# Messchieber.net
KiCad netlist of a schematic drawn in EAGLE
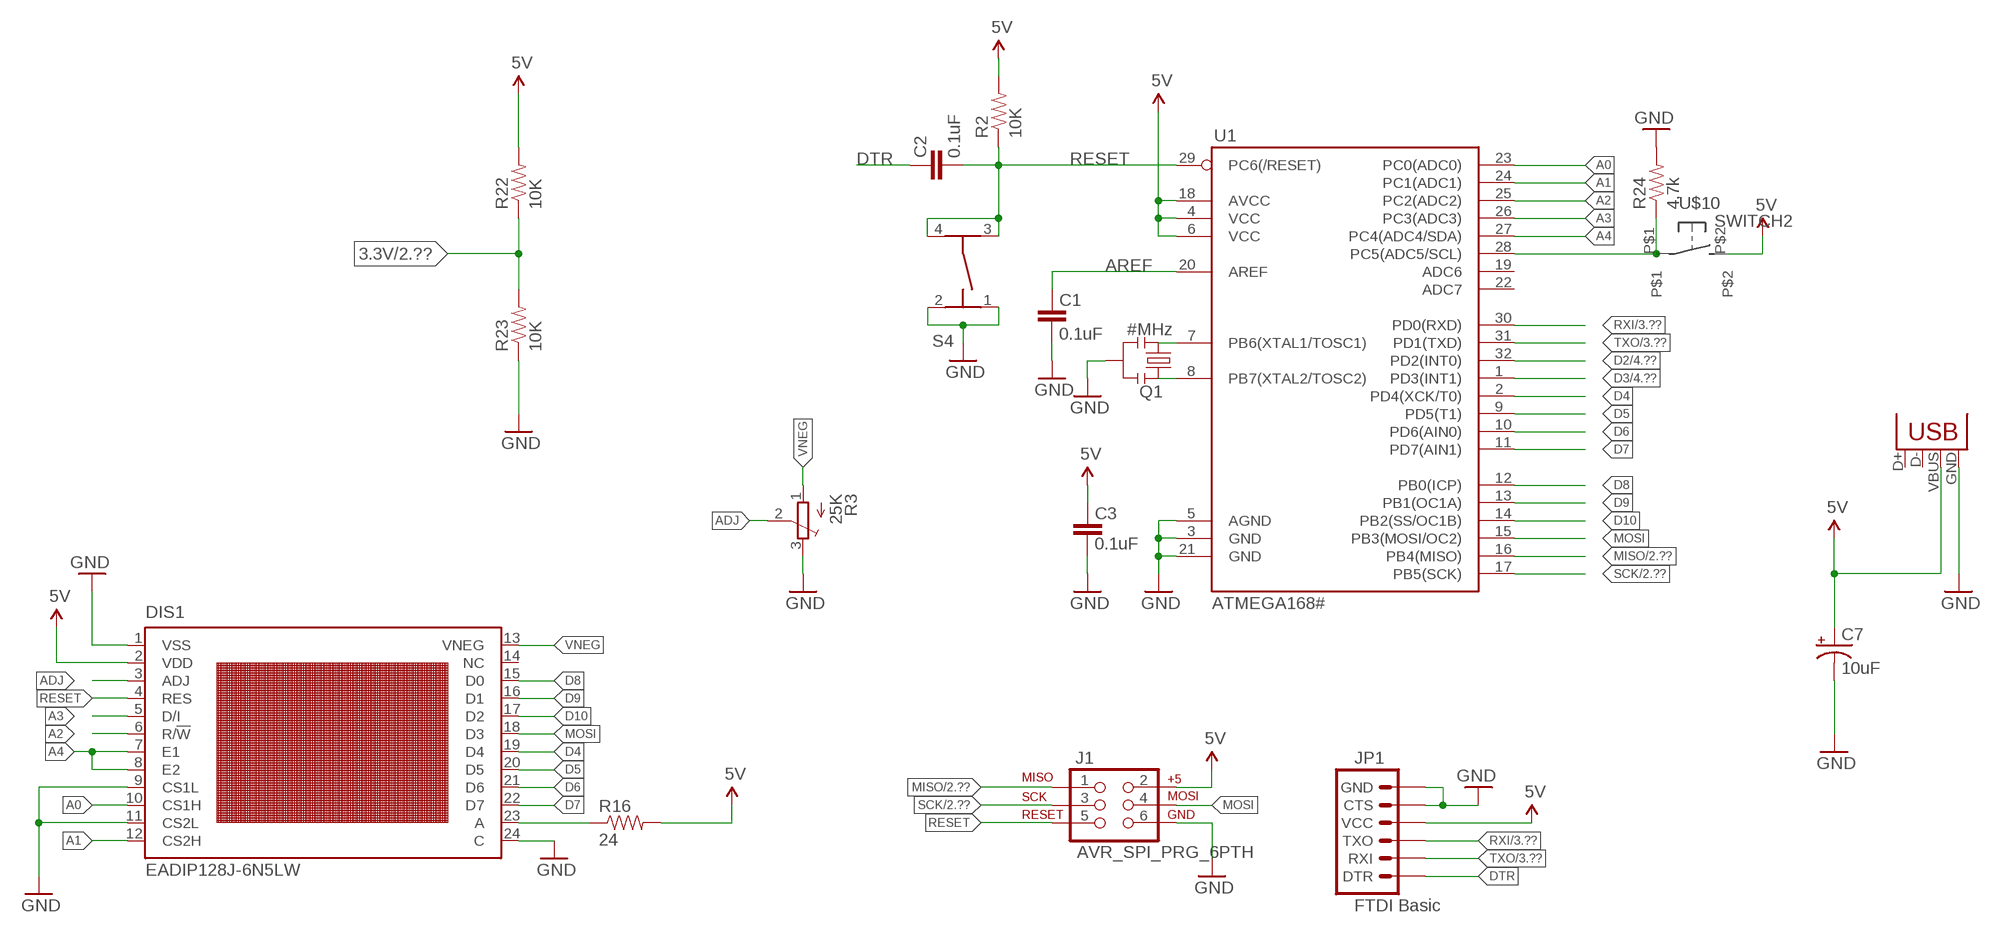
[diagram p0: schematic, sheet 1]
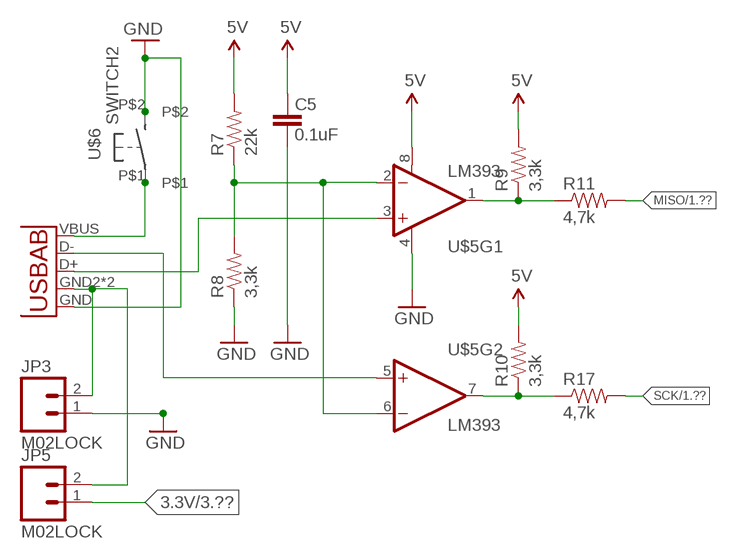
[diagram p1: schematic, sheet 2]
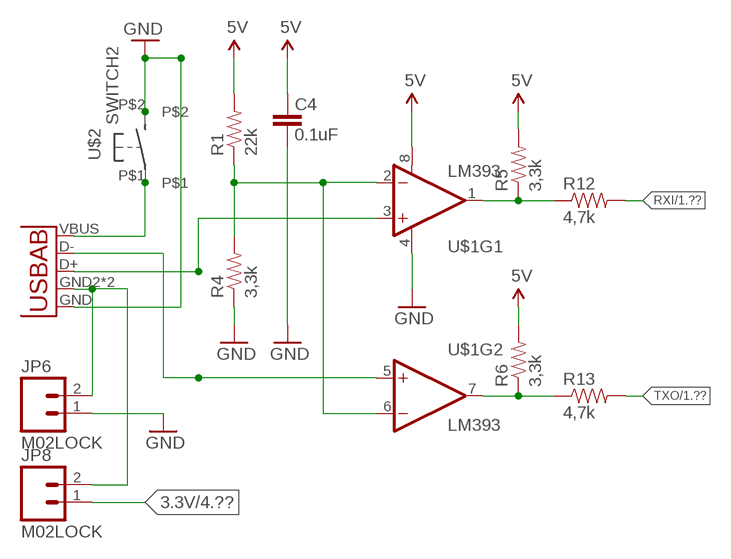
[diagram p2: schematic, sheet 3]
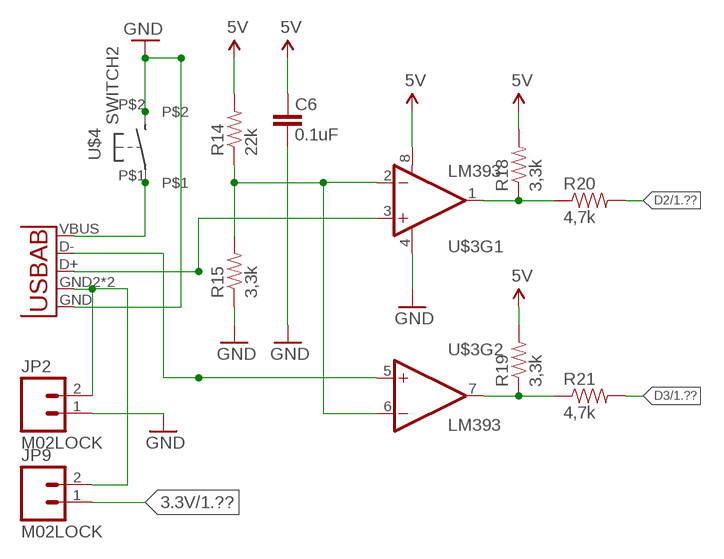
[diagram p3: schematic, sheet 4]

(export (version "E")
  (design (tool "Eeschema 10.0.6"))
  (components
    (comp (ref "C5")
      (value "0.1uF")
      (footprint "eagle-import:0805")
      (libsource (lib "eagle-import") (part "CAP0805"))
    )
    (comp (ref "JP3")
      (value "M02LOCK")
      (footprint "eagle-import:1X02_LOCK")
      (libsource (lib "eagle-import") (part "M02LOCK"))
    )
    (comp (ref "JP5")
      (value "M02LOCK")
      (footprint "eagle-import:1X02_LOCK")
      (libsource (lib "eagle-import") (part "M02LOCK"))
    )
    (comp (ref "R7")
      (value "22k")
      (footprint "eagle-import:0805")
      (libsource (lib "eagle-import") (part "RESISTOR"))
    )
    (comp (ref "R8")
      (value "3,3k")
      (footprint "eagle-import:0805")
      (libsource (lib "eagle-import") (part "RESISTOR"))
    )
    (comp (ref "R9")
      (value "3,3k")
      (footprint "eagle-import:0805")
      (libsource (lib "eagle-import") (part "RESISTOR"))
    )
    (comp (ref "R10")
      (value "3,3k")
      (footprint "eagle-import:0805")
      (libsource (lib "eagle-import") (part "RESISTOR"))
    )
    (comp (ref "R11")
      (value "4,7k")
      (footprint "eagle-import:0805")
      (libsource (lib "eagle-import") (part "RESISTOR"))
    )
    (comp (ref "R17")
      (value "4,7k")
      (footprint "eagle-import:0805")
      (libsource (lib "eagle-import") (part "RESISTOR"))
    )
    (comp (ref "U$5")
      (value "LM393")
      (footprint "eagle-import:SO08")
      (libsource (lib "eagle-import") (part "LM393"))
    )
    (comp (ref "U$6")
      (value "SWITCH2")
      (footprint "eagle-import:SWITCH2")
      (libsource (lib "eagle-import") (part "SWITCH2"))
    )
    (comp (ref "U$7")
      (value "USB-A")
      (footprint "eagle-import:USB-A")
      (libsource (lib "eagle-import") (part "USB-A"))
    )
    (comp (ref "C4")
      (value "0.1uF")
      (footprint "eagle-import:0805")
      (libsource (lib "eagle-import") (part "CAP0805"))
    )
    (comp (ref "JP6")
      (value "M02LOCK")
      (footprint "eagle-import:1X02_LOCK")
      (libsource (lib "eagle-import") (part "M02LOCK"))
    )
    (comp (ref "JP8")
      (value "M02LOCK")
      (footprint "eagle-import:1X02_LOCK")
      (libsource (lib "eagle-import") (part "M02LOCK"))
    )
    (comp (ref "R1")
      (value "22k")
      (footprint "eagle-import:0805")
      (libsource (lib "eagle-import") (part "RESISTOR"))
    )
    (comp (ref "R4")
      (value "3,3k")
      (footprint "eagle-import:0805")
      (libsource (lib "eagle-import") (part "RESISTOR"))
    )
    (comp (ref "R5")
      (value "3,3k")
      (footprint "eagle-import:0805")
      (libsource (lib "eagle-import") (part "RESISTOR"))
    )
    (comp (ref "R6")
      (value "3,3k")
      (footprint "eagle-import:0805")
      (libsource (lib "eagle-import") (part "RESISTOR"))
    )
    (comp (ref "R12")
      (value "4,7k")
      (footprint "eagle-import:0805")
      (libsource (lib "eagle-import") (part "RESISTOR"))
    )
    (comp (ref "R13")
      (value "4,7k")
      (footprint "eagle-import:0805")
      (libsource (lib "eagle-import") (part "RESISTOR"))
    )
    (comp (ref "U$1")
      (value "LM393")
      (footprint "eagle-import:SO08")
      (libsource (lib "eagle-import") (part "LM393"))
    )
    (comp (ref "U$2")
      (value "SWITCH2")
      (footprint "eagle-import:SWITCH2")
      (libsource (lib "eagle-import") (part "SWITCH2"))
    )
    (comp (ref "U$8")
      (value "USB-A")
      (footprint "eagle-import:USB-A")
      (libsource (lib "eagle-import") (part "USB-A"))
    )
    (comp (ref "C6")
      (value "0.1uF")
      (footprint "eagle-import:0805")
      (libsource (lib "eagle-import") (part "CAP0805"))
    )
    (comp (ref "JP2")
      (value "M02LOCK")
      (footprint "eagle-import:1X02_LOCK")
      (libsource (lib "eagle-import") (part "M02LOCK"))
    )
    (comp (ref "JP9")
      (value "M02LOCK")
      (footprint "eagle-import:1X02_LOCK")
      (libsource (lib "eagle-import") (part "M02LOCK"))
    )
    (comp (ref "R14")
      (value "22k")
      (footprint "eagle-import:0805")
      (libsource (lib "eagle-import") (part "RESISTOR"))
    )
    (comp (ref "R15")
      (value "3,3k")
      (footprint "eagle-import:0805")
      (libsource (lib "eagle-import") (part "RESISTOR"))
    )
    (comp (ref "R18")
      (value "3,3k")
      (footprint "eagle-import:0805")
      (libsource (lib "eagle-import") (part "RESISTOR"))
    )
    (comp (ref "R19")
      (value "3,3k")
      (footprint "eagle-import:0805")
      (libsource (lib "eagle-import") (part "RESISTOR"))
    )
    (comp (ref "R20")
      (value "4,7k")
      (footprint "eagle-import:0805")
      (libsource (lib "eagle-import") (part "RESISTOR"))
    )
    (comp (ref "R21")
      (value "4,7k")
      (footprint "eagle-import:0805")
      (libsource (lib "eagle-import") (part "RESISTOR"))
    )
    (comp (ref "U$3")
      (value "LM393")
      (footprint "eagle-import:SO08")
      (libsource (lib "eagle-import") (part "LM393"))
    )
    (comp (ref "U$4")
      (value "SWITCH2")
      (footprint "eagle-import:SWITCH2")
      (libsource (lib "eagle-import") (part "SWITCH2"))
    )
    (comp (ref "U$9")
      (value "USB-A")
      (footprint "eagle-import:USB-A")
      (libsource (lib "eagle-import") (part "USB-A"))
    )
    (comp (ref "C1")
      (value "0.1uF")
      (footprint "eagle-import:0805")
      (libsource (lib "eagle-import") (part "CAP0805"))
    )
    (comp (ref "C2")
      (value "0.1uF")
      (footprint "eagle-import:0805")
      (libsource (lib "eagle-import") (part "CAP0805"))
    )
    (comp (ref "C3")
      (value "0.1uF")
      (footprint "eagle-import:0805")
      (libsource (lib "eagle-import") (part "CAP0805"))
    )
    (comp (ref "C7")
      (value "10uF")
      (footprint "eagle-import:EIA3216")
      (libsource (lib "eagle-import") (part "10UF-16V-10%(TANT)"))
    )
    (comp (ref "DIS1")
      (value "EADIP128J-6N5LW")
      (footprint "eagle-import:LCD-DIP128-64")
      (libsource (lib "eagle-import") (part "EADIP128-6N5LWJ"))
    )
    (comp (ref "J1")
      (value "AVR_SPI_PRG_6PTH")
      (footprint "eagle-import:2X3")
      (libsource (lib "eagle-import") (part "AVR_SPI_PRG_6PTH"))
    )
    (comp (ref "JP1")
      (value "FTDI Basic")
      (footprint "eagle-import:1X06")
      (libsource (lib "eagle-import") (part "ARDUINO_SERIAL_PROGRAMPTH"))
    )
    (comp (ref "JP7")
      (value "USB-SMD-NS")
      (footprint "eagle-import:USB-MINIB-NOSTOP")
      (libsource (lib "eagle-import") (part "USB-SMD-NS"))
    )
    (comp (ref "Q1")
      (value "#MHz")
      (footprint "eagle-import:RESONATOR-SMD")
      (libsource (lib "eagle-import") (part "RESONATORSMD"))
    )
    (comp (ref "R2")
      (value "10K")
      (footprint "eagle-import:0805")
      (libsource (lib "eagle-import") (part "RESISTOR"))
    )
    (comp (ref "R3")
      (value "25K")
      (footprint "eagle-import:SM-42_43A")
      (libsource (lib "eagle-import") (part "TRIM_EU-SM-42/43A"))
    )
    (comp (ref "R16")
      (value "24")
      (footprint "eagle-import:0805")
      (libsource (lib "eagle-import") (part "RESISTOR"))
    )
    (comp (ref "R22")
      (value "10K")
      (footprint "eagle-import:0805")
      (libsource (lib "eagle-import") (part "RESISTOR"))
    )
    (comp (ref "R23")
      (value "10K")
      (footprint "eagle-import:0805")
      (libsource (lib "eagle-import") (part "RESISTOR"))
    )
    (comp (ref "R24")
      (value "4,7k")
      (footprint "eagle-import:0805")
      (libsource (lib "eagle-import") (part "RESISTOR"))
    )
    (comp (ref "S4")
      (value "TASTER-9314_SMD")
      (footprint "eagle-import:TASTER-9314_SMD")
      (libsource (lib "eagle-import") (part "TASTER-9314_SMD"))
    )
    (comp (ref "U$10")
      (value "SWITCH2")
      (footprint "eagle-import:SWITCH2")
      (libsource (lib "eagle-import") (part "SWITCH2"))
    )
    (comp (ref "U1")
      (value "ATMEGA168#")
      (footprint "eagle-import:TQFP32-08")
      (libsource (lib "eagle-import") (part "ATMEGA168"))
    )
  )
  (nets
    (net (code "1") (name "3.3V") (class "Default")
      (node (ref "JP5") (pin "1") (pinfunction "1_1") (pintype "passive"))
      (node (ref "JP8") (pin "1") (pinfunction "1_1") (pintype "passive"))
      (node (ref "JP9") (pin "1") (pinfunction "1_1") (pintype "passive"))
      (node (ref "R22") (pin "1") (pinfunction "1_1") (pintype "passive"))
      (node (ref "R23") (pin "2") (pinfunction "2_2") (pintype "passive"))
    )
    (net (code "2") (name "5V") (class "Default")
      (node (ref "C3") (pin "2") (pinfunction "2_2") (pintype "passive"))
      (node (ref "C4") (pin "2") (pinfunction "2_2") (pintype "passive"))
      (node (ref "C5") (pin "2") (pinfunction "2_2") (pintype "passive"))
      (node (ref "C6") (pin "2") (pinfunction "2_2") (pintype "passive"))
      (node (ref "C7") (pin "A") (pinfunction "+_A") (pintype "passive"))
      (node (ref "DIS1") (pin "2") (pinfunction "VDD_2") (pintype "power_in"))
      (node (ref "J1") (pin "2") (pinfunction "2_2") (pintype "passive"))
      (node (ref "JP1") (pin "4") (pinfunction "VCC_4") (pintype "passive"))
      (node (ref "JP7") (pin "VBUS") (pinfunction "VBUS_VBUS") (pintype "bidirectional"))
      (node (ref "R1") (pin "2") (pinfunction "2_2") (pintype "passive"))
      (node (ref "R10") (pin "2") (pinfunction "2_2") (pintype "passive"))
      (node (ref "R14") (pin "2") (pinfunction "2_2") (pintype "passive"))
      (node (ref "R16") (pin "2") (pinfunction "2_2") (pintype "passive"))
      (node (ref "R18") (pin "2") (pinfunction "2_2") (pintype "passive"))
      (node (ref "R19") (pin "2") (pinfunction "2_2") (pintype "passive"))
      (node (ref "R2") (pin "2") (pinfunction "2_2") (pintype "passive"))
      (node (ref "R22") (pin "2") (pinfunction "2_2") (pintype "passive"))
      (node (ref "R5") (pin "2") (pinfunction "2_2") (pintype "passive"))
      (node (ref "R6") (pin "2") (pinfunction "2_2") (pintype "passive"))
      (node (ref "R7") (pin "2") (pinfunction "2_2") (pintype "passive"))
      (node (ref "R9") (pin "2") (pinfunction "2_2") (pintype "passive"))
      (node (ref "U$1") (pin "8") (pinfunction "V+_8") (pintype "power_in"))
      (node (ref "U$10") (pin "P$2") (pinfunction "P$2_P$2") (pintype "bidirectional"))
      (node (ref "U$3") (pin "8") (pinfunction "V+_8") (pintype "power_in"))
      (node (ref "U$5") (pin "8") (pinfunction "V+_8") (pintype "power_in"))
      (node (ref "U1") (pin "18") (pinfunction "AVCC_18") (pintype "bidirectional"))
      (node (ref "U1") (pin "4") (pinfunction "VCC_4") (pintype "bidirectional"))
      (node (ref "U1") (pin "6") (pinfunction "VCC_6") (pintype "bidirectional"))
    )
    (net (code "3") (name "A0") (class "Default")
      (node (ref "DIS1") (pin "10") (pinfunction "CS1H_10") (pintype "input"))
      (node (ref "U1") (pin "23") (pinfunction "PC0(ADC0)_23") (pintype "bidirectional"))
    )
    (net (code "4") (name "A1") (class "Default")
      (node (ref "DIS1") (pin "12") (pinfunction "CS2H_12") (pintype "input"))
      (node (ref "U1") (pin "24") (pinfunction "PC1(ADC1)_24") (pintype "bidirectional"))
    )
    (net (code "5") (name "A2") (class "Default")
      (node (ref "DIS1") (pin "6") (pinfunction "R/~{W}_6") (pintype "input"))
      (node (ref "U1") (pin "25") (pinfunction "PC2(ADC2)_25") (pintype "bidirectional"))
    )
    (net (code "6") (name "A3") (class "Default")
      (node (ref "DIS1") (pin "5") (pinfunction "D/I_5") (pintype "input"))
      (node (ref "U1") (pin "26") (pinfunction "PC3(ADC3)_26") (pintype "bidirectional"))
    )
    (net (code "7") (name "A4") (class "Default")
      (node (ref "DIS1") (pin "7") (pinfunction "E1_7") (pintype "input"))
      (node (ref "DIS1") (pin "8") (pinfunction "E2_8") (pintype "input"))
      (node (ref "U1") (pin "27") (pinfunction "PC4(ADC4/SDA)_27") (pintype "bidirectional"))
    )
    (net (code "8") (name "ADJ") (class "Default")
      (node (ref "DIS1") (pin "3") (pinfunction "ADJ_3") (pintype "input"))
      (node (ref "R3") (pin "2") (pinfunction "S_2") (pintype "passive"))
    )
    (net (code "9") (name "AREF") (class "Default")
      (node (ref "C1") (pin "2") (pinfunction "2_2") (pintype "passive"))
      (node (ref "U1") (pin "20") (pinfunction "AREF_20") (pintype "bidirectional"))
    )
    (net (code "10") (name "D2") (class "Default")
      (node (ref "R20") (pin "2") (pinfunction "2_2") (pintype "passive"))
      (node (ref "U1") (pin "32") (pinfunction "PD2(INT0)_32") (pintype "bidirectional"))
    )
    (net (code "11") (name "D3") (class "Default")
      (node (ref "R21") (pin "2") (pinfunction "2_2") (pintype "passive"))
      (node (ref "U1") (pin "1") (pinfunction "PD3(INT1)_1") (pintype "bidirectional"))
    )
    (net (code "12") (name "D4") (class "Default")
      (node (ref "DIS1") (pin "19") (pinfunction "D4_19") (pintype "bidirectional"))
      (node (ref "U1") (pin "2") (pinfunction "PD4(XCK/T0)_2") (pintype "bidirectional"))
    )
    (net (code "13") (name "D5") (class "Default")
      (node (ref "DIS1") (pin "20") (pinfunction "D5_20") (pintype "bidirectional"))
      (node (ref "U1") (pin "9") (pinfunction "PD5(T1)_9") (pintype "bidirectional"))
    )
    (net (code "14") (name "D6") (class "Default")
      (node (ref "DIS1") (pin "21") (pinfunction "D6_21") (pintype "bidirectional"))
      (node (ref "U1") (pin "10") (pinfunction "PD6(AIN0)_10") (pintype "bidirectional"))
    )
    (net (code "15") (name "D7") (class "Default")
      (node (ref "DIS1") (pin "22") (pinfunction "D7_22") (pintype "bidirectional"))
      (node (ref "U1") (pin "11") (pinfunction "PD7(AIN1)_11") (pintype "bidirectional"))
    )
    (net (code "16") (name "D8") (class "Default")
      (node (ref "DIS1") (pin "15") (pinfunction "D0_15") (pintype "bidirectional"))
      (node (ref "U1") (pin "12") (pinfunction "PB0(ICP)_12") (pintype "bidirectional"))
    )
    (net (code "17") (name "D9") (class "Default")
      (node (ref "DIS1") (pin "16") (pinfunction "D1_16") (pintype "bidirectional"))
      (node (ref "U1") (pin "13") (pinfunction "PB1(OC1A)_13") (pintype "bidirectional"))
    )
    (net (code "18") (name "D10") (class "Default")
      (node (ref "DIS1") (pin "17") (pinfunction "D2_17") (pintype "bidirectional"))
      (node (ref "U1") (pin "14") (pinfunction "PB2(SS/OC1B)_14") (pintype "bidirectional"))
    )
    (net (code "19") (name "DTR") (class "Default")
      (node (ref "C2") (pin "2") (pinfunction "2_2") (pintype "passive"))
      (node (ref "JP1") (pin "1") (pinfunction "DTR_1") (pintype "passive"))
    )
    (net (code "20") (name "GND") (class "Default")
      (node (ref "C1") (pin "1") (pinfunction "1_1") (pintype "passive"))
      (node (ref "C3") (pin "1") (pinfunction "1_1") (pintype "passive"))
      (node (ref "C4") (pin "1") (pinfunction "1_1") (pintype "passive"))
      (node (ref "C5") (pin "1") (pinfunction "1_1") (pintype "passive"))
      (node (ref "C6") (pin "1") (pinfunction "1_1") (pintype "passive"))
      (node (ref "C7") (pin "C") (pinfunction "-_C") (pintype "passive"))
      (node (ref "DIS1") (pin "1") (pinfunction "VSS_1") (pintype "power_in"))
      (node (ref "DIS1") (pin "11") (pinfunction "CS2L_11") (pintype "input"))
      (node (ref "DIS1") (pin "24") (pinfunction "C_24") (pintype "passive"))
      (node (ref "DIS1") (pin "9") (pinfunction "CS1L_9") (pintype "input"))
      (node (ref "J1") (pin "6") (pinfunction "6_6") (pintype "passive"))
      (node (ref "JP1") (pin "5") (pinfunction "CTS_5") (pintype "passive"))
      (node (ref "JP1") (pin "6") (pinfunction "GND_6") (pintype "passive"))
      (node (ref "JP2") (pin "1") (pinfunction "1_1") (pintype "passive"))
      (node (ref "JP3") (pin "1") (pinfunction "1_1") (pintype "passive"))
      (node (ref "JP6") (pin "1") (pinfunction "1_1") (pintype "passive"))
      (node (ref "JP7") (pin "GND") (pinfunction "GND_GND") (pintype "bidirectional"))
      (node (ref "Q1") (pin "2") (pinfunction "2_2") (pintype "passive"))
      (node (ref "R15") (pin "1") (pinfunction "1_1") (pintype "passive"))
      (node (ref "R23") (pin "1") (pinfunction "1_1") (pintype "passive"))
      (node (ref "R24") (pin "2") (pinfunction "2_2") (pintype "passive"))
      (node (ref "R3") (pin "3") (pinfunction "E_3") (pintype "passive"))
      (node (ref "R4") (pin "1") (pinfunction "1_1") (pintype "passive"))
      (node (ref "R8") (pin "1") (pinfunction "1_1") (pintype "passive"))
      (node (ref "S4") (pin "1") (pinfunction "1_1") (pintype "passive"))
      (node (ref "S4") (pin "2") (pinfunction "2_2") (pintype "passive"))
      (node (ref "U$1") (pin "4") (pinfunction "V-_4") (pintype "power_in"))
      (node (ref "U$2") (pin "P$2") (pinfunction "P$2_P$2") (pintype "bidirectional"))
      (node (ref "U$3") (pin "4") (pinfunction "V-_4") (pintype "power_in"))
      (node (ref "U$4") (pin "P$2") (pinfunction "P$2_P$2") (pintype "bidirectional"))
      (node (ref "U$5") (pin "4") (pinfunction "V-_4") (pintype "power_in"))
      (node (ref "U$6") (pin "P$2") (pinfunction "P$2_P$2") (pintype "bidirectional"))
      (node (ref "U$7") (pin "GND") (pinfunction "GND_GND") (pintype "bidirectional"))
      (node (ref "U$8") (pin "GND") (pinfunction "GND_GND") (pintype "bidirectional"))
      (node (ref "U$9") (pin "GND") (pinfunction "GND_GND") (pintype "bidirectional"))
      (node (ref "U1") (pin "21") (pinfunction "GND_21") (pintype "bidirectional"))
      (node (ref "U1") (pin "3") (pinfunction "GND_3") (pintype "bidirectional"))
      (node (ref "U1") (pin "5") (pinfunction "AGND_5") (pintype "bidirectional"))
    )
    (net (code "21") (name "MISO") (class "Default")
      (node (ref "J1") (pin "1") (pinfunction "1_1") (pintype "passive"))
      (node (ref "R11") (pin "2") (pinfunction "2_2") (pintype "passive"))
      (node (ref "U1") (pin "16") (pinfunction "PB4(MISO)_16") (pintype "bidirectional"))
    )
    (net (code "22") (name "MOSI") (class "Default")
      (node (ref "DIS1") (pin "18") (pinfunction "D3_18") (pintype "bidirectional"))
      (node (ref "J1") (pin "4") (pinfunction "4_4") (pintype "passive"))
      (node (ref "U1") (pin "15") (pinfunction "PB3(MOSI/OC2)_15") (pintype "bidirectional"))
    )
    (net (code "23") (name "Net-(DIS1-A)") (class "Default")
      (node (ref "DIS1") (pin "23") (pinfunction "A_23") (pintype "passive"))
      (node (ref "R16") (pin "1") (pinfunction "1_1") (pintype "passive"))
    )
    (net (code "24") (name "Net-(JP2-Pad2)") (class "Default")
      (node (ref "JP2") (pin "2") (pinfunction "2_2") (pintype "passive"))
      (node (ref "JP9") (pin "2") (pinfunction "2_2") (pintype "passive"))
      (node (ref "U$9") (pin "GND2") (pinfunction "USBID_GND2") (pintype "bidirectional"))
      (node (ref "U$9") (pin "GND3") (pinfunction "USBID_GND3") (pintype "bidirectional"))
    )
    (net (code "25") (name "Net-(JP3-Pad2)") (class "Default")
      (node (ref "JP3") (pin "2") (pinfunction "2_2") (pintype "passive"))
      (node (ref "JP5") (pin "2") (pinfunction "2_2") (pintype "passive"))
      (node (ref "U$7") (pin "GND2") (pinfunction "USBID_GND2") (pintype "bidirectional"))
      (node (ref "U$7") (pin "GND3") (pinfunction "USBID_GND3") (pintype "bidirectional"))
    )
    (net (code "26") (name "Net-(JP6-Pad2)") (class "Default")
      (node (ref "JP6") (pin "2") (pinfunction "2_2") (pintype "passive"))
      (node (ref "JP8") (pin "2") (pinfunction "2_2") (pintype "passive"))
      (node (ref "U$8") (pin "GND2") (pinfunction "USBID_GND2") (pintype "bidirectional"))
      (node (ref "U$8") (pin "GND3") (pinfunction "USBID_GND3") (pintype "bidirectional"))
    )
    (net (code "27") (name "Net-(U$1A-+IN)") (class "Default")
      (node (ref "U$1") (pin "3") (pinfunction "+IN_3") (pintype "input"))
      (node (ref "U$8") (pin "D+") (pinfunction "D+_D+") (pintype "bidirectional"))
    )
    (net (code "28") (name "Net-(U$1A--IN)") (class "Default")
      (node (ref "R1") (pin "1") (pinfunction "1_1") (pintype "passive"))
      (node (ref "R4") (pin "2") (pinfunction "2_2") (pintype "passive"))
      (node (ref "U$1") (pin "2") (pinfunction "-IN_2") (pintype "input"))
      (node (ref "U$1") (pin "6") (pinfunction "-IN_6") (pintype "input"))
    )
    (net (code "29") (name "Net-(U$1A-OUT)") (class "Default")
      (node (ref "R12") (pin "1") (pinfunction "1_1") (pintype "passive"))
      (node (ref "R5") (pin "1") (pinfunction "1_1") (pintype "passive"))
      (node (ref "U$1") (pin "1") (pinfunction "OUT_1") (pintype "output"))
    )
    (net (code "30") (name "Net-(U$1B-+IN)") (class "Default")
      (node (ref "U$1") (pin "5") (pinfunction "+IN_5") (pintype "input"))
      (node (ref "U$8") (pin "D-") (pinfunction "D-_D-") (pintype "bidirectional"))
    )
    (net (code "31") (name "Net-(U$1B-OUT)") (class "Default")
      (node (ref "R13") (pin "1") (pinfunction "1_1") (pintype "passive"))
      (node (ref "R6") (pin "1") (pinfunction "1_1") (pintype "passive"))
      (node (ref "U$1") (pin "7") (pinfunction "OUT_7") (pintype "output"))
    )
    (net (code "32") (name "Net-(U$2-PadP$1)") (class "Default")
      (node (ref "U$2") (pin "P$1") (pinfunction "P$1_P$1") (pintype "bidirectional"))
      (node (ref "U$8") (pin "VBUS") (pinfunction "VBUS_VBUS") (pintype "bidirectional"))
    )
    (net (code "33") (name "Net-(U$3A-+IN)") (class "Default")
      (node (ref "U$3") (pin "3") (pinfunction "+IN_3") (pintype "input"))
      (node (ref "U$9") (pin "D+") (pinfunction "D+_D+") (pintype "bidirectional"))
    )
    (net (code "34") (name "Net-(U$3A--IN)") (class "Default")
      (node (ref "R14") (pin "1") (pinfunction "1_1") (pintype "passive"))
      (node (ref "R15") (pin "2") (pinfunction "2_2") (pintype "passive"))
      (node (ref "U$3") (pin "2") (pinfunction "-IN_2") (pintype "input"))
      (node (ref "U$3") (pin "6") (pinfunction "-IN_6") (pintype "input"))
    )
    (net (code "35") (name "Net-(U$3A-OUT)") (class "Default")
      (node (ref "R18") (pin "1") (pinfunction "1_1") (pintype "passive"))
      (node (ref "R20") (pin "1") (pinfunction "1_1") (pintype "passive"))
      (node (ref "U$3") (pin "1") (pinfunction "OUT_1") (pintype "output"))
    )
    (net (code "36") (name "Net-(U$3B-+IN)") (class "Default")
      (node (ref "U$3") (pin "5") (pinfunction "+IN_5") (pintype "input"))
      (node (ref "U$9") (pin "D-") (pinfunction "D-_D-") (pintype "bidirectional"))
    )
    (net (code "37") (name "Net-(U$3B-OUT)") (class "Default")
      (node (ref "R19") (pin "1") (pinfunction "1_1") (pintype "passive"))
      (node (ref "R21") (pin "1") (pinfunction "1_1") (pintype "passive"))
      (node (ref "U$3") (pin "7") (pinfunction "OUT_7") (pintype "output"))
    )
    (net (code "38") (name "Net-(U$4-PadP$1)") (class "Default")
      (node (ref "U$4") (pin "P$1") (pinfunction "P$1_P$1") (pintype "bidirectional"))
      (node (ref "U$9") (pin "VBUS") (pinfunction "VBUS_VBUS") (pintype "bidirectional"))
    )
    (net (code "39") (name "Net-(U$5A-+IN)") (class "Default")
      (node (ref "U$5") (pin "3") (pinfunction "+IN_3") (pintype "input"))
      (node (ref "U$7") (pin "D+") (pinfunction "D+_D+") (pintype "bidirectional"))
    )
    (net (code "40") (name "Net-(U$5A--IN)") (class "Default")
      (node (ref "R7") (pin "1") (pinfunction "1_1") (pintype "passive"))
      (node (ref "R8") (pin "2") (pinfunction "2_2") (pintype "passive"))
      (node (ref "U$5") (pin "2") (pinfunction "-IN_2") (pintype "input"))
      (node (ref "U$5") (pin "6") (pinfunction "-IN_6") (pintype "input"))
    )
    (net (code "41") (name "Net-(U$5A-OUT)") (class "Default")
      (node (ref "R11") (pin "1") (pinfunction "1_1") (pintype "passive"))
      (node (ref "R9") (pin "1") (pinfunction "1_1") (pintype "passive"))
      (node (ref "U$5") (pin "1") (pinfunction "OUT_1") (pintype "output"))
    )
    (net (code "42") (name "Net-(U$5B-+IN)") (class "Default")
      (node (ref "U$5") (pin "5") (pinfunction "+IN_5") (pintype "input"))
      (node (ref "U$7") (pin "D-") (pinfunction "D-_D-") (pintype "bidirectional"))
    )
    (net (code "43") (name "Net-(U$5B-OUT)") (class "Default")
      (node (ref "R10") (pin "1") (pinfunction "1_1") (pintype "passive"))
      (node (ref "R17") (pin "1") (pinfunction "1_1") (pintype "passive"))
      (node (ref "U$5") (pin "7") (pinfunction "OUT_7") (pintype "output"))
    )
    (net (code "44") (name "Net-(U$6-PadP$1)") (class "Default")
      (node (ref "U$6") (pin "P$1") (pinfunction "P$1_P$1") (pintype "bidirectional"))
      (node (ref "U$7") (pin "VBUS") (pinfunction "VBUS_VBUS") (pintype "bidirectional"))
    )
    (net (code "45") (name "Net-(U1-PB6(XTAL1{slash}TOSC1))") (class "Default")
      (node (ref "Q1") (pin "3") (pinfunction "3_3") (pintype "passive"))
      (node (ref "U1") (pin "7") (pinfunction "PB6(XTAL1/TOSC1)_7") (pintype "bidirectional"))
    )
    (net (code "46") (name "Net-(U1-PB7(XTAL2{slash}TOSC2))") (class "Default")
      (node (ref "Q1") (pin "1") (pinfunction "1_1") (pintype "passive"))
      (node (ref "U1") (pin "8") (pinfunction "PB7(XTAL2/TOSC2)_8") (pintype "bidirectional"))
    )
    (net (code "47") (name "Net-(U1-PC5(ADC5{slash}SCL))") (class "Default")
      (node (ref "R24") (pin "1") (pinfunction "1_1") (pintype "passive"))
      (node (ref "U$10") (pin "P$1") (pinfunction "P$1_P$1") (pintype "bidirectional"))
      (node (ref "U1") (pin "28") (pinfunction "PC5(ADC5/SCL)_28") (pintype "bidirectional"))
    )
    (net (code "48") (name "RESET") (class "Default")
      (node (ref "C2") (pin "1") (pinfunction "1_1") (pintype "passive"))
      (node (ref "DIS1") (pin "4") (pinfunction "RES_4") (pintype "input"))
      (node (ref "J1") (pin "5") (pinfunction "5_5") (pintype "passive"))
      (node (ref "R2") (pin "1") (pinfunction "1_1") (pintype "passive"))
      (node (ref "S4") (pin "3") (pinfunction "3_3") (pintype "passive"))
      (node (ref "S4") (pin "4") (pinfunction "4_4") (pintype "passive"))
      (node (ref "U1") (pin "29") (pinfunction "PC6(/RESET)_29") (pintype "bidirectional"))
    )
    (net (code "49") (name "RXI") (class "Default")
      (node (ref "JP1") (pin "3") (pinfunction "TXO_3") (pintype "passive"))
      (node (ref "R12") (pin "2") (pinfunction "2_2") (pintype "passive"))
      (node (ref "U1") (pin "30") (pinfunction "PD0(RXD)_30") (pintype "bidirectional"))
    )
    (net (code "50") (name "SCK") (class "Default")
      (node (ref "J1") (pin "3") (pinfunction "3_3") (pintype "passive"))
      (node (ref "R17") (pin "2") (pinfunction "2_2") (pintype "passive"))
      (node (ref "U1") (pin "17") (pinfunction "PB5(SCK)_17") (pintype "bidirectional"))
    )
    (net (code "51") (name "TXO") (class "Default")
      (node (ref "JP1") (pin "2") (pinfunction "RXI_2") (pintype "passive"))
      (node (ref "R13") (pin "2") (pinfunction "2_2") (pintype "passive"))
      (node (ref "U1") (pin "31") (pinfunction "PD1(TXD)_31") (pintype "bidirectional"))
    )
    (net (code "52") (name "VNEG") (class "Default")
      (node (ref "DIS1") (pin "13") (pinfunction "VNEG_13") (pintype "passive"))
      (node (ref "R3") (pin "1") (pinfunction "A_1") (pintype "passive"))
    )
    (net (code "53") (name "unconnected-(DIS1-NC-Pad14)") (class "Default")
      (node (ref "DIS1") (pin "14") (pinfunction "NC_14") (pintype "no_connect"))
    )
    (net (code "54") (name "unconnected-(JP7-PadD+)") (class "Default")
      (node (ref "JP7") (pin "D+") (pinfunction "D+_D+") (pintype "bidirectional"))
    )
    (net (code "55") (name "unconnected-(JP7-PadD-)") (class "Default")
      (node (ref "JP7") (pin "D-") (pinfunction "D-_D-") (pintype "bidirectional"))
    )
    (net (code "56") (name "unconnected-(U1-ADC6-Pad19)") (class "Default")
      (node (ref "U1") (pin "19") (pinfunction "ADC6_19") (pintype "bidirectional"))
    )
    (net (code "57") (name "unconnected-(U1-ADC7-Pad22)") (class "Default")
      (node (ref "U1") (pin "22") (pinfunction "ADC7_22") (pintype "bidirectional"))
    )
  )
)
